# AC_load.net
KiCad netlist of a schematic drawn in EAGLE
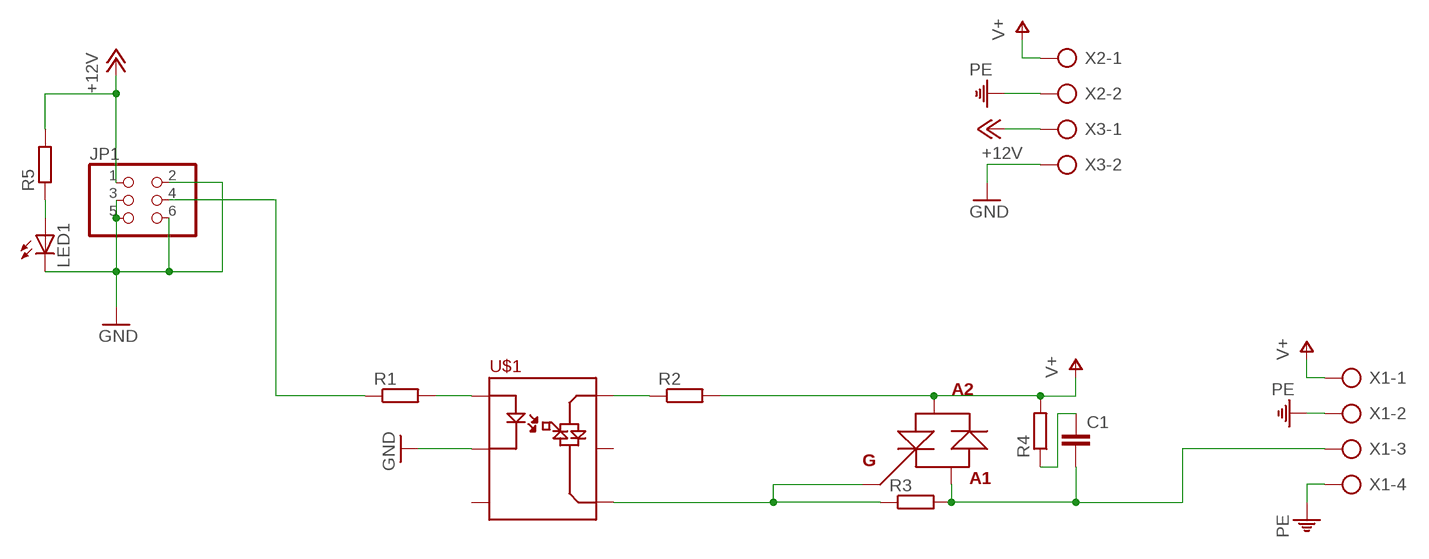
[diagram p0: schematic, sheet 1]

(export (version "E")
  (design (tool "Eeschema 10.0.6"))
  (components
    (comp (ref "C1")
      (value "C-EU102-064X133")
      (footprint "eagle-import:C102-064X133")
      (libsource (lib "eagle-import") (part "C-EU102-064X133"))
    )
    (comp (ref "JP1")
      (value "PINHD-2X3")
      (footprint "eagle-import:2X03")
      (libsource (lib "eagle-import") (part "PINHD-2X3"))
    )
    (comp (ref "LED1")
      (value "LEDSML1206")
      (footprint "eagle-import:SML1206")
      (libsource (lib "eagle-import") (part "LEDSML1206"))
    )
    (comp (ref "R1")
      (value "R-EU_M1206")
      (footprint "eagle-import:M1206")
      (libsource (lib "eagle-import") (part "R-EU_M1206"))
    )
    (comp (ref "R2")
      (value "R-EU_M1206")
      (footprint "eagle-import:M1206")
      (libsource (lib "eagle-import") (part "R-EU_M1206"))
    )
    (comp (ref "R3")
      (value "R-EU_M1206")
      (footprint "eagle-import:M1206")
      (libsource (lib "eagle-import") (part "R-EU_M1206"))
    )
    (comp (ref "R4")
      (value "R-EU_M1206")
      (footprint "eagle-import:M1206")
      (libsource (lib "eagle-import") (part "R-EU_M1206"))
    )
    (comp (ref "R5")
      (value "R-EU_M1206")
      (footprint "eagle-import:M1206")
      (libsource (lib "eagle-import") (part "R-EU_M1206"))
    )
    (comp (ref "U$1")
      (value "MOC3043")
      (footprint "eagle-import:DIL06")
      (libsource (lib "eagle-import") (part "MOC3043"))
    )
    (comp (ref "U$2")
      (value "BTB16")
      (footprint "eagle-import:TO220NORM")
      (libsource (lib "eagle-import") (part "BTB16"))
    )
    (comp (ref "X1")
      (value "AK500/4")
      (footprint "eagle-import:AK500_4")
      (libsource (lib "eagle-import") (part "AK500/4"))
    )
    (comp (ref "X2")
      (value "AK500/2")
      (footprint "eagle-import:AK500_2")
      (libsource (lib "eagle-import") (part "AK500/2"))
    )
    (comp (ref "X3")
      (value "AK500/2")
      (footprint "eagle-import:AK500_2")
      (libsource (lib "eagle-import") (part "AK500/2"))
    )
  )
  (nets
    (net (code "1") (name "+12V") (class "Default")
      (node (ref "JP1") (pin "1") (pinfunction "1_1") (pintype "passive"))
      (node (ref "R5") (pin "2") (pinfunction "2_2") (pintype "passive"))
      (node (ref "X3") (pin "1") (pinfunction "KL_1") (pintype "passive"))
    )
    (net (code "2") (name "GND") (class "Default")
      (node (ref "JP1") (pin "2") (pinfunction "2_2") (pintype "passive"))
      (node (ref "JP1") (pin "3") (pinfunction "3_3") (pintype "passive"))
      (node (ref "JP1") (pin "5") (pinfunction "5_5") (pintype "passive"))
      (node (ref "JP1") (pin "6") (pinfunction "6_6") (pintype "passive"))
      (node (ref "LED1") (pin "C") (pinfunction "C_C") (pintype "passive"))
      (node (ref "U$1") (pin "2") (pinfunction "LED_OUT_2") (pintype "bidirectional"))
      (node (ref "X3") (pin "2") (pinfunction "KL_2") (pintype "passive"))
    )
    (net (code "3") (name "Net-(C1-Pad1)") (class "Default")
      (node (ref "C1") (pin "1") (pinfunction "1_1") (pintype "passive"))
      (node (ref "R4") (pin "1") (pinfunction "1_1") (pintype "passive"))
    )
    (net (code "4") (name "Net-(JP1-Pad4)") (class "Default")
      (node (ref "JP1") (pin "4") (pinfunction "4_4") (pintype "passive"))
      (node (ref "R1") (pin "1") (pinfunction "1_1") (pintype "passive"))
    )
    (net (code "5") (name "Net-(LED1-PadA)") (class "Default")
      (node (ref "LED1") (pin "A") (pinfunction "A_A") (pintype "passive"))
      (node (ref "R5") (pin "1") (pinfunction "1_1") (pintype "passive"))
    )
    (net (code "6") (name "Net-(U$1-LED_IN)") (class "Default")
      (node (ref "R1") (pin "2") (pinfunction "2_2") (pintype "passive"))
      (node (ref "U$1") (pin "1") (pinfunction "LED_IN_1") (pintype "bidirectional"))
    )
    (net (code "7") (name "Net-(U$1-SIM1)") (class "Default")
      (node (ref "R2") (pin "1") (pinfunction "1_1") (pintype "passive"))
      (node (ref "U$1") (pin "6") (pinfunction "SIM1_6") (pintype "bidirectional"))
    )
    (net (code "8") (name "Net-(U$1-SIM2)") (class "Default")
      (node (ref "R3") (pin "1") (pinfunction "1_1") (pintype "passive"))
      (node (ref "U$1") (pin "4") (pinfunction "SIM2_4") (pintype "bidirectional"))
      (node (ref "U$2") (pin "GATE") (pinfunction "G_GATE") (pintype "bidirectional"))
    )
    (net (code "9") (name "Net-(U$2-A1)") (class "Default")
      (node (ref "C1") (pin "2") (pinfunction "2_2") (pintype "passive"))
      (node (ref "R3") (pin "2") (pinfunction "2_2") (pintype "passive"))
      (node (ref "U$2") (pin "MT1") (pinfunction "A1_MT1") (pintype "bidirectional"))
      (node (ref "X1") (pin "3") (pinfunction "KL_3") (pintype "passive"))
    )
    (net (code "10") (name "PE") (class "Default")
      (node (ref "X1") (pin "2") (pinfunction "KL_2") (pintype "passive"))
      (node (ref "X1") (pin "4") (pinfunction "KL_4") (pintype "passive"))
      (node (ref "X2") (pin "2") (pinfunction "KL_2") (pintype "passive"))
    )
    (net (code "11") (name "V+") (class "Default")
      (node (ref "R2") (pin "2") (pinfunction "2_2") (pintype "passive"))
      (node (ref "R4") (pin "2") (pinfunction "2_2") (pintype "passive"))
      (node (ref "U$2") (pin "MT2") (pinfunction "A2_MT2") (pintype "bidirectional"))
      (node (ref "X1") (pin "1") (pinfunction "KL_1") (pintype "passive"))
      (node (ref "X2") (pin "1") (pinfunction "KL_1") (pintype "passive"))
    )
    (net (code "12") (name "unconnected-(U$1-N{slash}C-Pad3)") (class "Default")
      (node (ref "U$1") (pin "3") (pinfunction "N/C_3") (pintype "bidirectional"))
    )
    (net (code "13") (name "unconnected-(U$1-N{slash}C2-Pad5)") (class "Default")
      (node (ref "U$1") (pin "5") (pinfunction "N/C2_5") (pintype "bidirectional"))
    )
  )
)
